# DemoBB_1289.net
KiCad netlist of a schematic drawn in EAGLE
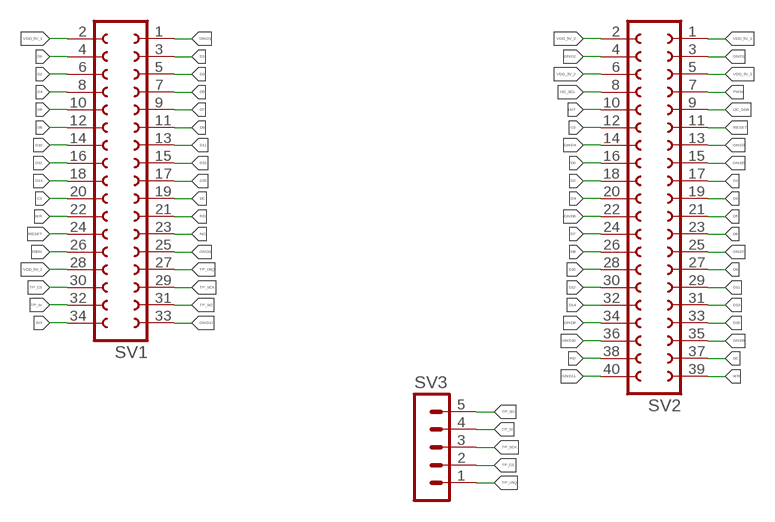
[diagram p0: schematic, sheet 1]

(export (version "E")
  (design (tool "Eeschema 10.0.6"))
  (components
    (comp (ref "SV1")
      (value "FE17-2")
      (footprint "eagle-import:FE17-2")
      (libsource (lib "eagle-import") (part "FE17-2"))
    )
    (comp (ref "SV2")
      (value "FE20-2")
      (footprint "eagle-import:FE20-2")
      (libsource (lib "eagle-import") (part "FE20-2"))
    )
    (comp (ref "SV3")
      (value "MA05-1")
      (footprint "eagle-import:MA05-1")
      (libsource (lib "eagle-import") (part "MA05-1"))
    )
  )
  (nets
    (net (code "1") (name "3V3") (class "Default")
      (node (ref "SV1") (pin "34") (pinfunction "34_34") (pintype "passive"))
    )
    (net (code "2") (name "CS") (class "Default")
      (node (ref "SV1") (pin "20") (pinfunction "20_20") (pintype "passive"))
      (node (ref "SV2") (pin "12") (pinfunction "12_12") (pintype "passive"))
    )
    (net (code "3") (name "D0") (class "Default")
      (node (ref "SV1") (pin "4") (pinfunction "4_4") (pintype "passive"))
      (node (ref "SV2") (pin "16") (pinfunction "16_16") (pintype "passive"))
    )
    (net (code "4") (name "D1") (class "Default")
      (node (ref "SV1") (pin "3") (pinfunction "3_3") (pintype "passive"))
      (node (ref "SV2") (pin "17") (pinfunction "17_17") (pintype "passive"))
    )
    (net (code "5") (name "D2") (class "Default")
      (node (ref "SV1") (pin "6") (pinfunction "6_6") (pintype "passive"))
      (node (ref "SV2") (pin "18") (pinfunction "18_18") (pintype "passive"))
    )
    (net (code "6") (name "D3") (class "Default")
      (node (ref "SV1") (pin "5") (pinfunction "5_5") (pintype "passive"))
      (node (ref "SV2") (pin "19") (pinfunction "19_19") (pintype "passive"))
    )
    (net (code "7") (name "D4") (class "Default")
      (node (ref "SV1") (pin "8") (pinfunction "8_8") (pintype "passive"))
      (node (ref "SV2") (pin "20") (pinfunction "20_20") (pintype "passive"))
    )
    (net (code "8") (name "D5") (class "Default")
      (node (ref "SV1") (pin "7") (pinfunction "7_7") (pintype "passive"))
      (node (ref "SV2") (pin "21") (pinfunction "21_21") (pintype "passive"))
    )
    (net (code "9") (name "D6") (class "Default")
      (node (ref "SV1") (pin "10") (pinfunction "10_10") (pintype "passive"))
      (node (ref "SV2") (pin "23") (pinfunction "23_23") (pintype "passive"))
    )
    (net (code "10") (name "D7") (class "Default")
      (node (ref "SV1") (pin "9") (pinfunction "9_9") (pintype "passive"))
      (node (ref "SV2") (pin "24") (pinfunction "24_24") (pintype "passive"))
    )
    (net (code "11") (name "D8") (class "Default")
      (node (ref "SV1") (pin "12") (pinfunction "12_12") (pintype "passive"))
      (node (ref "SV2") (pin "26") (pinfunction "26_26") (pintype "passive"))
    )
    (net (code "12") (name "D9") (class "Default")
      (node (ref "SV1") (pin "11") (pinfunction "11_11") (pintype "passive"))
      (node (ref "SV2") (pin "27") (pinfunction "27_27") (pintype "passive"))
    )
    (net (code "13") (name "D10") (class "Default")
      (node (ref "SV1") (pin "14") (pinfunction "14_14") (pintype "passive"))
      (node (ref "SV2") (pin "28") (pinfunction "28_28") (pintype "passive"))
    )
    (net (code "14") (name "D11") (class "Default")
      (node (ref "SV1") (pin "13") (pinfunction "13_13") (pintype "passive"))
      (node (ref "SV2") (pin "29") (pinfunction "29_29") (pintype "passive"))
    )
    (net (code "15") (name "D12") (class "Default")
      (node (ref "SV1") (pin "16") (pinfunction "16_16") (pintype "passive"))
      (node (ref "SV2") (pin "30") (pinfunction "30_30") (pintype "passive"))
    )
    (net (code "16") (name "D13") (class "Default")
      (node (ref "SV1") (pin "15") (pinfunction "15_15") (pintype "passive"))
      (node (ref "SV2") (pin "31") (pinfunction "31_31") (pintype "passive"))
    )
    (net (code "17") (name "D14") (class "Default")
      (node (ref "SV1") (pin "18") (pinfunction "18_18") (pintype "passive"))
      (node (ref "SV2") (pin "32") (pinfunction "32_32") (pintype "passive"))
    )
    (net (code "18") (name "D15") (class "Default")
      (node (ref "SV1") (pin "17") (pinfunction "17_17") (pintype "passive"))
      (node (ref "SV2") (pin "33") (pinfunction "33_33") (pintype "passive"))
    )
    (net (code "19") (name "DC") (class "Default")
      (node (ref "SV1") (pin "19") (pinfunction "19_19") (pintype "passive"))
      (node (ref "SV2") (pin "37") (pinfunction "37_37") (pintype "passive"))
    )
    (net (code "20") (name "GND1") (class "Default")
      (node (ref "SV1") (pin "1") (pinfunction "1_1") (pintype "passive"))
      (node (ref "SV2") (pin "3") (pinfunction "3_3") (pintype "passive"))
    )
    (net (code "21") (name "GND2") (class "Default")
      (node (ref "SV1") (pin "25") (pinfunction "25_25") (pintype "passive"))
      (node (ref "SV2") (pin "4") (pinfunction "4_4") (pintype "passive"))
    )
    (net (code "22") (name "GND3") (class "Default")
      (node (ref "SV2") (pin "13") (pinfunction "13_13") (pintype "passive"))
    )
    (net (code "23") (name "GND4") (class "Default")
      (node (ref "SV2") (pin "14") (pinfunction "14_14") (pintype "passive"))
    )
    (net (code "24") (name "GND5") (class "Default")
      (node (ref "SV2") (pin "15") (pinfunction "15_15") (pintype "passive"))
    )
    (net (code "25") (name "GND6") (class "Default")
      (node (ref "SV2") (pin "22") (pinfunction "22_22") (pintype "passive"))
    )
    (net (code "26") (name "GND7") (class "Default")
      (node (ref "SV2") (pin "25") (pinfunction "25_25") (pintype "passive"))
    )
    (net (code "27") (name "GND8") (class "Default")
      (node (ref "SV2") (pin "34") (pinfunction "34_34") (pintype "passive"))
    )
    (net (code "28") (name "GND9") (class "Default")
      (node (ref "SV2") (pin "35") (pinfunction "35_35") (pintype "passive"))
    )
    (net (code "29") (name "GND10") (class "Default")
      (node (ref "SV2") (pin "36") (pinfunction "36_36") (pintype "passive"))
    )
    (net (code "30") (name "GND11") (class "Default")
      (node (ref "SV1") (pin "33") (pinfunction "33_33") (pintype "passive"))
      (node (ref "SV2") (pin "40") (pinfunction "40_40") (pintype "passive"))
    )
    (net (code "31") (name "I2C_SCL") (class "Default")
      (node (ref "SV2") (pin "8") (pinfunction "8_8") (pintype "passive"))
    )
    (net (code "32") (name "I2C_SDA") (class "Default")
      (node (ref "SV2") (pin "9") (pinfunction "9_9") (pintype "passive"))
    )
    (net (code "33") (name "INT") (class "Default")
      (node (ref "SV2") (pin "10") (pinfunction "10_10") (pintype "passive"))
    )
    (net (code "34") (name "N$62") (class "Default")
      (node (ref "SV1") (pin "26") (pinfunction "26_26") (pintype "passive"))
    )
    (net (code "35") (name "NC") (class "Default")
      (node (ref "SV1") (pin "23") (pinfunction "23_23") (pintype "passive"))
    )
    (net (code "36") (name "PWM") (class "Default")
      (node (ref "SV2") (pin "7") (pinfunction "7_7") (pintype "passive"))
    )
    (net (code "37") (name "RD") (class "Default")
      (node (ref "SV1") (pin "21") (pinfunction "21_21") (pintype "passive"))
      (node (ref "SV2") (pin "38") (pinfunction "38_38") (pintype "passive"))
    )
    (net (code "38") (name "RESET") (class "Default")
      (node (ref "SV1") (pin "24") (pinfunction "24_24") (pintype "passive"))
      (node (ref "SV2") (pin "11") (pinfunction "11_11") (pintype "passive"))
    )
    (net (code "39") (name "TP_CS") (class "Default")
      (node (ref "SV1") (pin "30") (pinfunction "30_30") (pintype "passive"))
      (node (ref "SV3") (pin "2") (pinfunction "2_2") (pintype "passive"))
    )
    (net (code "40") (name "TP_IRQ") (class "Default")
      (node (ref "SV1") (pin "27") (pinfunction "27_27") (pintype "passive"))
      (node (ref "SV3") (pin "1") (pinfunction "1_1") (pintype "passive"))
    )
    (net (code "41") (name "TP_SCK") (class "Default")
      (node (ref "SV1") (pin "29") (pinfunction "29_29") (pintype "passive"))
      (node (ref "SV3") (pin "3") (pinfunction "3_3") (pintype "passive"))
    )
    (net (code "42") (name "TP_SI") (class "Default")
      (node (ref "SV1") (pin "32") (pinfunction "32_32") (pintype "passive"))
      (node (ref "SV3") (pin "4") (pinfunction "4_4") (pintype "passive"))
    )
    (net (code "43") (name "TP_SO") (class "Default")
      (node (ref "SV1") (pin "31") (pinfunction "31_31") (pintype "passive"))
      (node (ref "SV3") (pin "5") (pinfunction "5_5") (pintype "passive"))
    )
    (net (code "44") (name "VDD_3V_1") (class "Default")
      (node (ref "SV2") (pin "5") (pinfunction "5_5") (pintype "passive"))
    )
    (net (code "45") (name "VDD_3V_2") (class "Default")
      (node (ref "SV2") (pin "6") (pinfunction "6_6") (pintype "passive"))
    )
    (net (code "46") (name "VDD_5V_1") (class "Default")
      (node (ref "SV1") (pin "2") (pinfunction "2_2") (pintype "passive"))
      (node (ref "SV2") (pin "1") (pinfunction "1_1") (pintype "passive"))
    )
    (net (code "47") (name "VDD_5V_2") (class "Default")
      (node (ref "SV1") (pin "28") (pinfunction "28_28") (pintype "passive"))
      (node (ref "SV2") (pin "2") (pinfunction "2_2") (pintype "passive"))
    )
    (net (code "48") (name "WR") (class "Default")
      (node (ref "SV1") (pin "22") (pinfunction "22_22") (pintype "passive"))
      (node (ref "SV2") (pin "39") (pinfunction "39_39") (pintype "passive"))
    )
  )
)
